# 20226.net
KiCad netlist of a schematic drawn in EAGLE
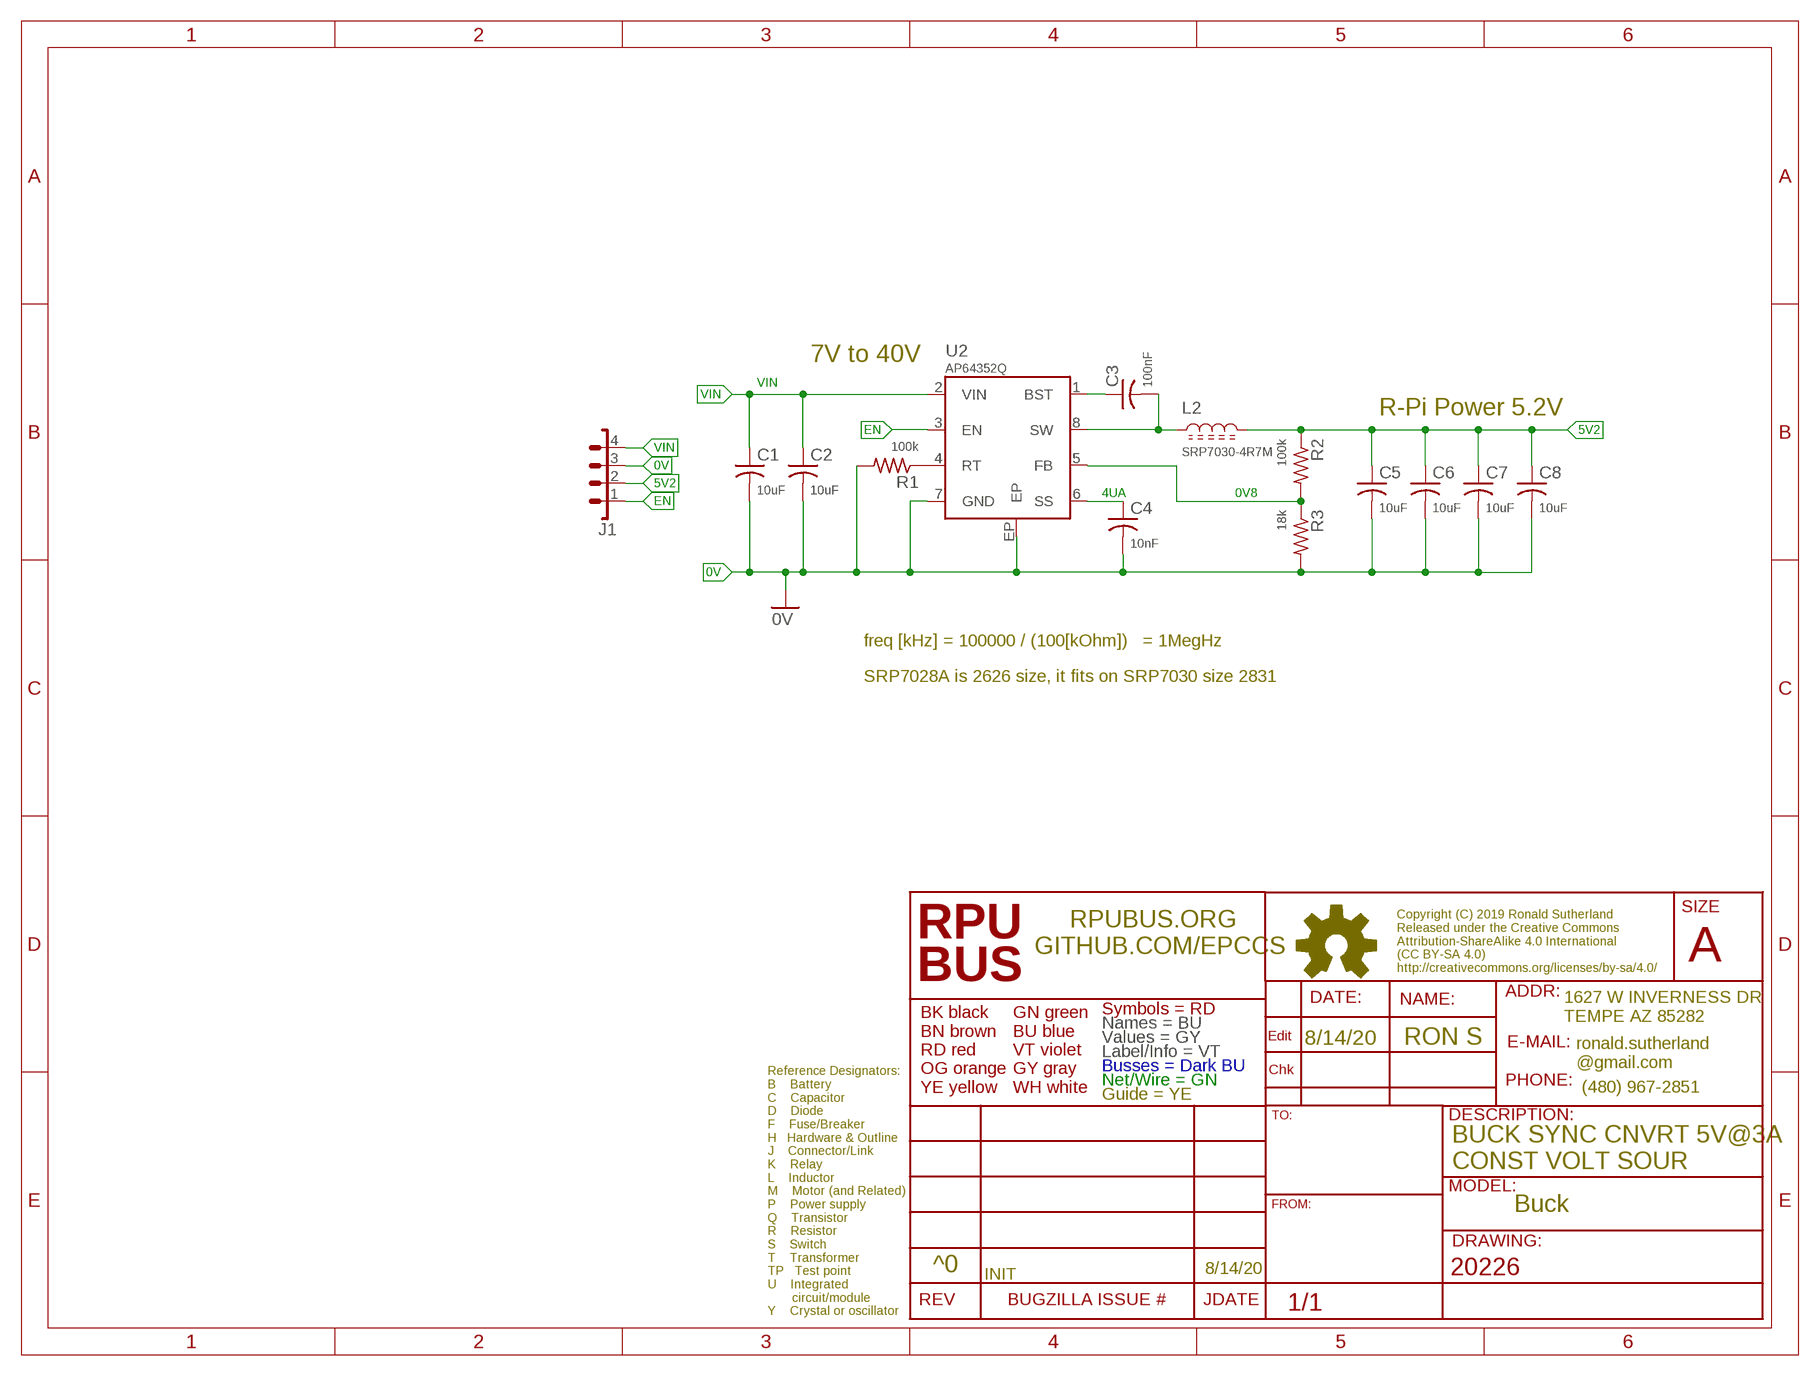
[diagram p0: schematic, sheet 1]

(export (version "E")
  (design (tool "Eeschema 10.0.6"))
  (components
    (comp (ref "C1")
      (value "10uF")
      (footprint "eagle-import:C1206(3216)")
      (libsource (lib "eagle-import") (part "CC1206"))
    )
    (comp (ref "C2")
      (value "10uF")
      (footprint "eagle-import:C1206(3216)")
      (libsource (lib "eagle-import") (part "CC1206"))
    )
    (comp (ref "C3")
      (value "100nF")
      (footprint "eagle-import:C0603(1608)")
      (libsource (lib "eagle-import") (part "CC0603A"))
    )
    (comp (ref "C4")
      (value "10nF")
      (footprint "eagle-import:C0603(1608)")
      (libsource (lib "eagle-import") (part "CC0603A"))
    )
    (comp (ref "C5")
      (value "10uF")
      (footprint "eagle-import:C1206(3216)")
      (libsource (lib "eagle-import") (part "CC1206"))
    )
    (comp (ref "C6")
      (value "10uF")
      (footprint "eagle-import:C1206(3216)")
      (libsource (lib "eagle-import") (part "CC1206"))
    )
    (comp (ref "C7")
      (value "10uF")
      (footprint "eagle-import:C1206(3216)")
      (libsource (lib "eagle-import") (part "CC1206"))
    )
    (comp (ref "C8")
      (value "10uF")
      (footprint "eagle-import:C1206(3216)")
      (libsource (lib "eagle-import") (part "CC1206"))
    )
    (comp (ref "J1")
      (value "1X4")
      (footprint "eagle-import:1X4")
      (libsource (lib "eagle-import") (part "1X4"))
    )
    (comp (ref "L2")
      (value "SRP7030-4R7M")
      (footprint "eagle-import:L2831")
      (libsource (lib "eagle-import") (part "L2831"))
    )
    (comp (ref "R1")
      (value "100k")
      (footprint "eagle-import:C0805(2012)")
      (libsource (lib "eagle-import") (part "R0805"))
    )
    (comp (ref "R2")
      (value "100k")
      (footprint "eagle-import:C0805(2012)")
      (libsource (lib "eagle-import") (part "R0805"))
    )
    (comp (ref "R3")
      (value "18k")
      (footprint "eagle-import:C0805(2012)")
      (libsource (lib "eagle-import") (part "R0805"))
    )
    (comp (ref "U2")
      (value "AP64352Q")
      (footprint "eagle-import:SOIC8EP")
      (libsource (lib "eagle-import") (part "AP64352Q"))
    )
  )
  (nets
    (net (code "1") (name "/0V8") (class "Default")
      (node (ref "R2") (pin "2") (pinfunction "2_2") (pintype "passive"))
      (node (ref "R3") (pin "1") (pinfunction "1_1") (pintype "passive"))
      (node (ref "U2") (pin "5") (pinfunction "FB_5") (pintype "passive"))
    )
    (net (code "2") (name "/4UA") (class "Default")
      (node (ref "C4") (pin "1") (pinfunction "1_1") (pintype "passive"))
      (node (ref "U2") (pin "6") (pinfunction "SS_6") (pintype "passive"))
    )
    (net (code "3") (name "0V") (class "Default")
      (node (ref "C1") (pin "2") (pinfunction "2_2") (pintype "passive"))
      (node (ref "C2") (pin "2") (pinfunction "2_2") (pintype "passive"))
      (node (ref "C4") (pin "2") (pinfunction "2_2") (pintype "passive"))
      (node (ref "C5") (pin "2") (pinfunction "2_2") (pintype "passive"))
      (node (ref "C6") (pin "2") (pinfunction "2_2") (pintype "passive"))
      (node (ref "C7") (pin "2") (pinfunction "2_2") (pintype "passive"))
      (node (ref "C8") (pin "2") (pinfunction "2_2") (pintype "passive"))
      (node (ref "J1") (pin "3") (pinfunction "3_3") (pintype "passive"))
      (node (ref "R1") (pin "2") (pinfunction "2_2") (pintype "passive"))
      (node (ref "R3") (pin "2") (pinfunction "2_2") (pintype "passive"))
      (node (ref "U2") (pin "7") (pinfunction "GND_7") (pintype "power_in"))
      (node (ref "U2") (pin "EP") (pinfunction "EP_EP") (pintype "passive"))
    )
    (net (code "4") (name "5V2") (class "Default")
      (node (ref "C5") (pin "1") (pinfunction "1_1") (pintype "passive"))
      (node (ref "C6") (pin "1") (pinfunction "1_1") (pintype "passive"))
      (node (ref "C7") (pin "1") (pinfunction "1_1") (pintype "passive"))
      (node (ref "C8") (pin "1") (pinfunction "1_1") (pintype "passive"))
      (node (ref "J1") (pin "2") (pinfunction "2_2") (pintype "passive"))
      (node (ref "L2") (pin "2") (pinfunction "2_2") (pintype "passive"))
      (node (ref "R2") (pin "1") (pinfunction "1_1") (pintype "passive"))
    )
    (net (code "5") (name "EN") (class "Default")
      (node (ref "J1") (pin "1") (pinfunction "1_1") (pintype "passive"))
      (node (ref "U2") (pin "3") (pinfunction "EN_3") (pintype "input"))
    )
    (net (code "6") (name "Net-(U2-BST)") (class "Default")
      (node (ref "C3") (pin "1") (pinfunction "1_1") (pintype "passive"))
      (node (ref "U2") (pin "1") (pinfunction "BST_1") (pintype "input"))
    )
    (net (code "7") (name "Net-(U2-RT)") (class "Default")
      (node (ref "R1") (pin "1") (pinfunction "1_1") (pintype "passive"))
      (node (ref "U2") (pin "4") (pinfunction "RT_4") (pintype "passive"))
    )
    (net (code "8") (name "Net-(U2-SW)") (class "Default")
      (node (ref "C3") (pin "2") (pinfunction "2_2") (pintype "passive"))
      (node (ref "L2") (pin "1") (pinfunction "1_1") (pintype "passive"))
      (node (ref "U2") (pin "8") (pinfunction "SW_8") (pintype "bidirectional"))
    )
    (net (code "9") (name "VIN") (class "Default")
      (node (ref "C1") (pin "1") (pinfunction "1_1") (pintype "passive"))
      (node (ref "C2") (pin "1") (pinfunction "1_1") (pintype "passive"))
      (node (ref "J1") (pin "4") (pinfunction "4_4") (pintype "passive"))
      (node (ref "U2") (pin "2") (pinfunction "VIN_2") (pintype "power_in"))
    )
  )
)
